# CT_main.net
KiCad netlist of a schematic drawn in EAGLE
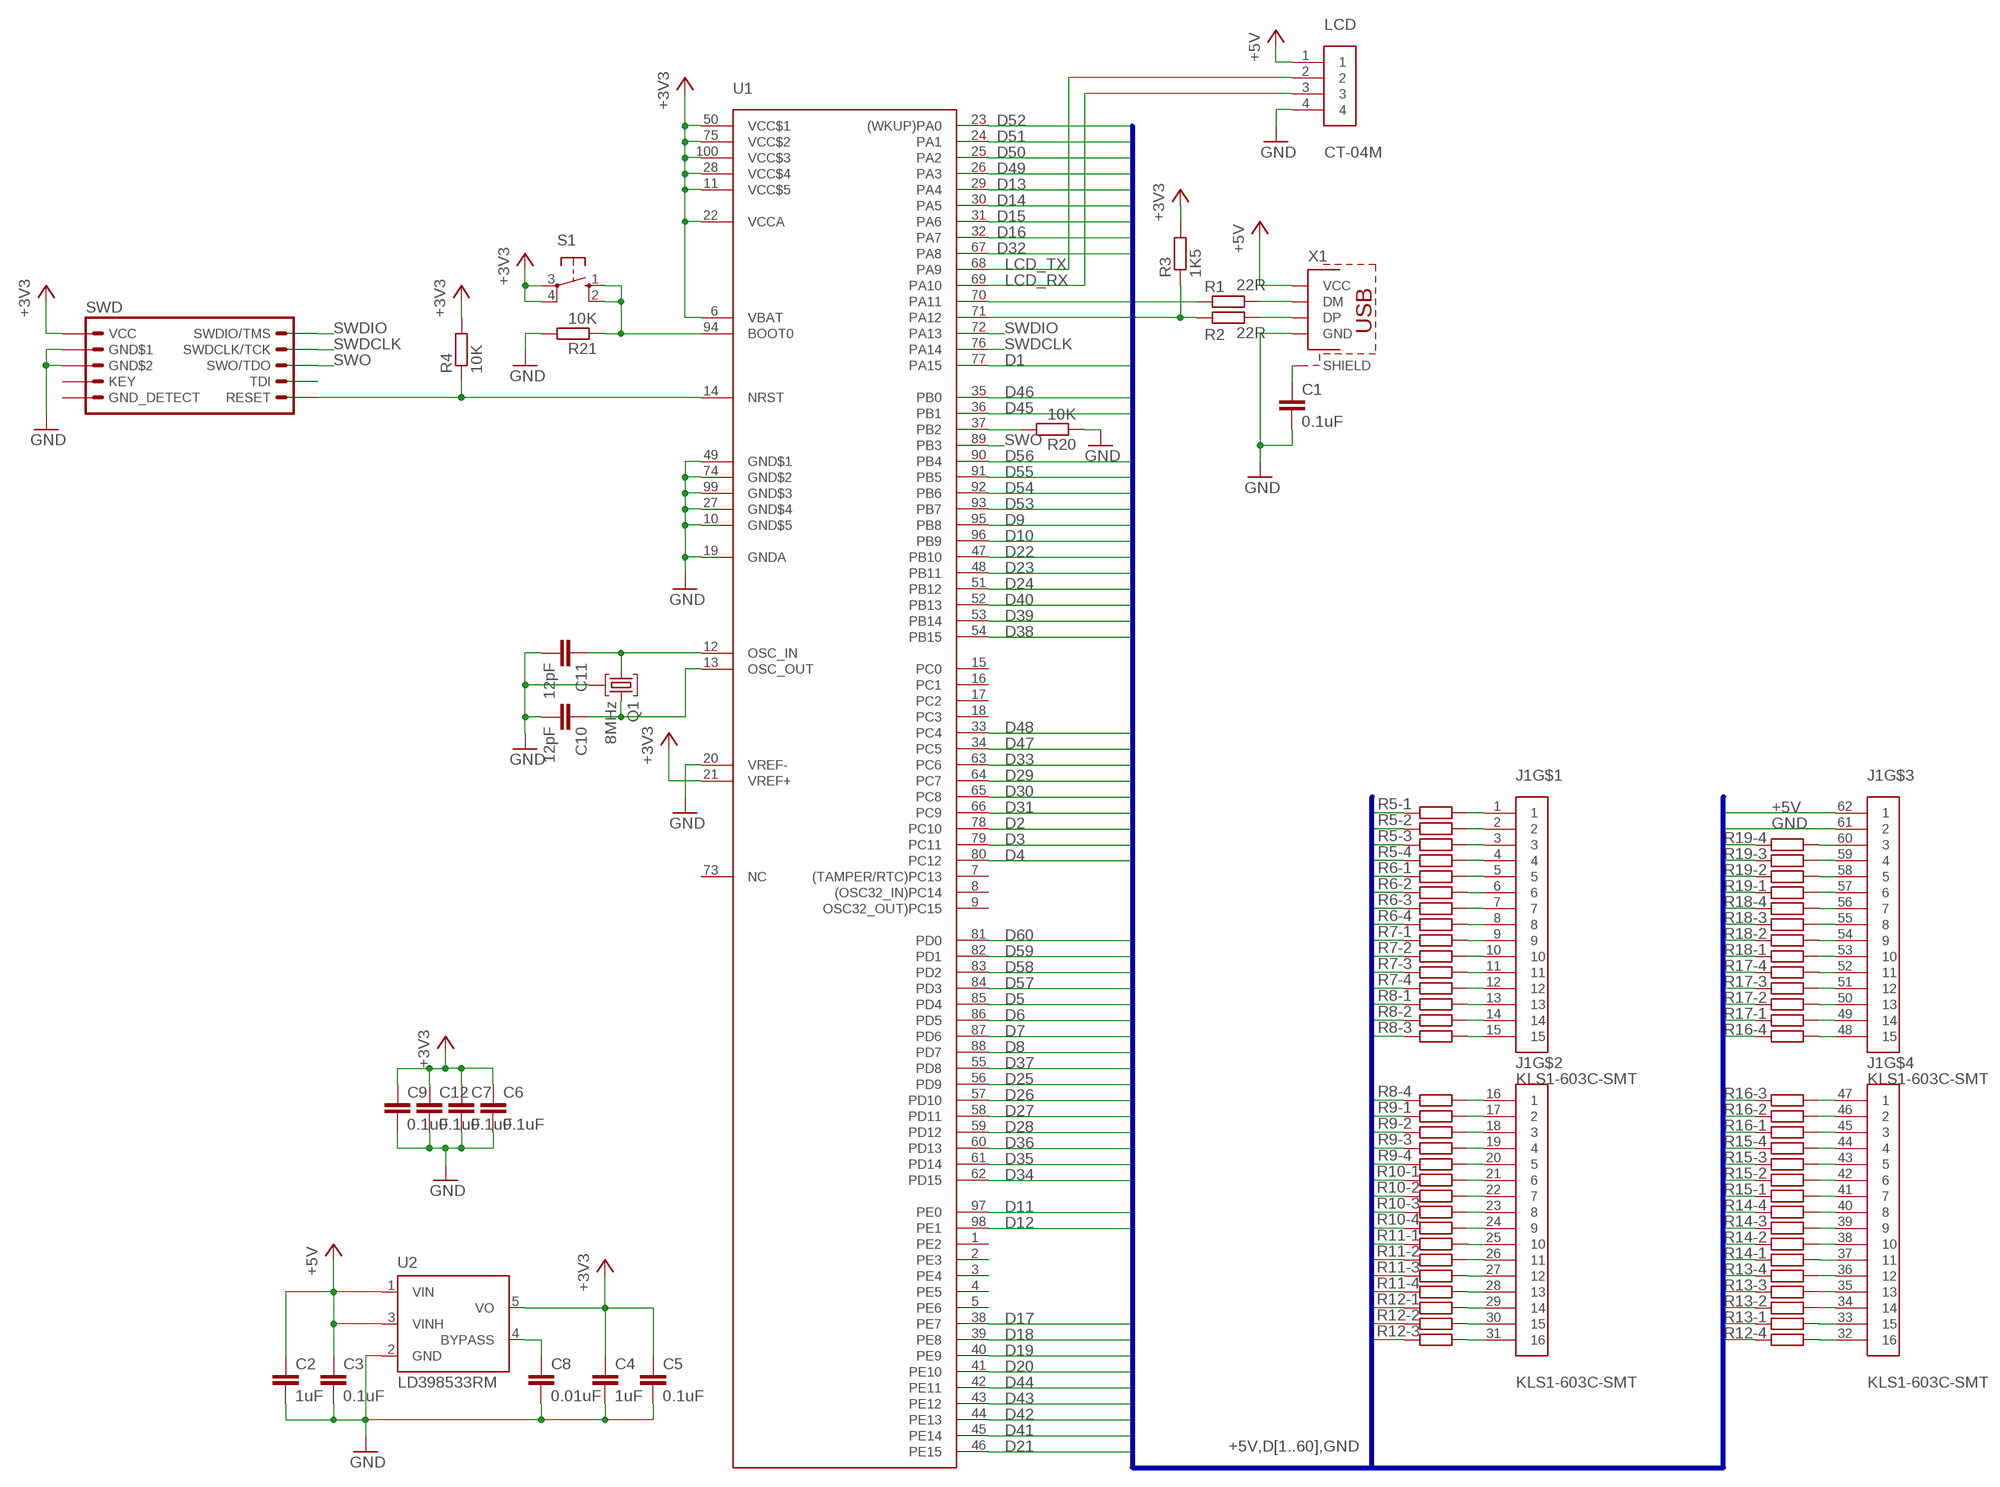
[diagram p0: schematic, sheet 1]

(export (version "E")
  (design (tool "Eeschema 10.0.6"))
  (components
    (comp (ref "C1")
      (value "0.1uF")
      (footprint "eagle-import:C0603")
      (libsource (lib "eagle-import") (part "C-EU_0603"))
    )
    (comp (ref "C2")
      (value "1uF")
      (footprint "eagle-import:C0603")
      (libsource (lib "eagle-import") (part "C-EU_0603"))
    )
    (comp (ref "C3")
      (value "0.1uF")
      (footprint "eagle-import:C0603")
      (libsource (lib "eagle-import") (part "C-EU_0603"))
    )
    (comp (ref "C4")
      (value "1uF")
      (footprint "eagle-import:C0603")
      (libsource (lib "eagle-import") (part "C-EU_0603"))
    )
    (comp (ref "C5")
      (value "0.1uF")
      (footprint "eagle-import:C0603")
      (libsource (lib "eagle-import") (part "C-EU_0603"))
    )
    (comp (ref "C6")
      (value "0.1uF")
      (footprint "eagle-import:C0603")
      (libsource (lib "eagle-import") (part "C-EU_0603"))
    )
    (comp (ref "C7")
      (value "0.1uF")
      (footprint "eagle-import:C0603")
      (libsource (lib "eagle-import") (part "C-EU_0603"))
    )
    (comp (ref "C8")
      (value "0.01uF")
      (footprint "eagle-import:C0603")
      (libsource (lib "eagle-import") (part "C-EU_0603"))
    )
    (comp (ref "C9")
      (value "0.1uF")
      (footprint "eagle-import:C0603")
      (libsource (lib "eagle-import") (part "C-EU_0603"))
    )
    (comp (ref "C10")
      (value "12pF")
      (footprint "eagle-import:C0603")
      (libsource (lib "eagle-import") (part "C-EU_0603"))
    )
    (comp (ref "C11")
      (value "12pF")
      (footprint "eagle-import:C0603")
      (libsource (lib "eagle-import") (part "C-EU_0603"))
    )
    (comp (ref "C12")
      (value "0.1uF")
      (footprint "eagle-import:C0603")
      (libsource (lib "eagle-import") (part "C-EU_0603"))
    )
    (comp (ref "J1")
      (value "KLS1-603C-SMT")
      (footprint "eagle-import:KLS1-603C-SMT")
      (libsource (lib "eagle-import") (part "KLS1-603C-SMT"))
    )
    (comp (ref "LCD")
      (value "CT-04M")
      (footprint "eagle-import:CT-04M")
      (libsource (lib "eagle-import") (part "CT-04M"))
    )
    (comp (ref "Q1")
      (value "8MHz")
      (footprint "eagle-import:KX-7_12.XXXXX")
      (libsource (lib "eagle-import") (part "CRYSTALKX-7_12.XXXXX"))
    )
    (comp (ref "R1")
      (value "22R")
      (footprint "eagle-import:R0603")
      (libsource (lib "eagle-import") (part "R-EU__0603"))
    )
    (comp (ref "R2")
      (value "22R")
      (footprint "eagle-import:R0603")
      (libsource (lib "eagle-import") (part "R-EU__0603"))
    )
    (comp (ref "R3")
      (value "1K5")
      (footprint "eagle-import:R0603")
      (libsource (lib "eagle-import") (part "R-EU__0603"))
    )
    (comp (ref "R4")
      (value "10K")
      (footprint "eagle-import:R0603")
      (libsource (lib "eagle-import") (part "R-EU__0603"))
    )
    (comp (ref "R5")
      (value "R_EU_4_R1206")
      (footprint "eagle-import:R1206_4")
      (libsource (lib "eagle-import") (part "R_EU_4_R1206"))
    )
    (comp (ref "R6")
      (value "R_EU_4_R1206")
      (footprint "eagle-import:R1206_4")
      (libsource (lib "eagle-import") (part "R_EU_4_R1206"))
    )
    (comp (ref "R7")
      (value "R_EU_4_R1206")
      (footprint "eagle-import:R1206_4")
      (libsource (lib "eagle-import") (part "R_EU_4_R1206"))
    )
    (comp (ref "R8")
      (value "R_EU_4_R1206")
      (footprint "eagle-import:R1206_4")
      (libsource (lib "eagle-import") (part "R_EU_4_R1206"))
    )
    (comp (ref "R9")
      (value "R_EU_4_R1206")
      (footprint "eagle-import:R1206_4")
      (libsource (lib "eagle-import") (part "R_EU_4_R1206"))
    )
    (comp (ref "R10")
      (value "R_EU_4_R1206")
      (footprint "eagle-import:R1206_4")
      (libsource (lib "eagle-import") (part "R_EU_4_R1206"))
    )
    (comp (ref "R11")
      (value "R_EU_4_R1206")
      (footprint "eagle-import:R1206_4")
      (libsource (lib "eagle-import") (part "R_EU_4_R1206"))
    )
    (comp (ref "R12")
      (value "R_EU_4_R1206")
      (footprint "eagle-import:R1206_4")
      (libsource (lib "eagle-import") (part "R_EU_4_R1206"))
    )
    (comp (ref "R13")
      (value "R_EU_4_R1206")
      (footprint "eagle-import:R1206_4")
      (libsource (lib "eagle-import") (part "R_EU_4_R1206"))
    )
    (comp (ref "R14")
      (value "R_EU_4_R1206")
      (footprint "eagle-import:R1206_4")
      (libsource (lib "eagle-import") (part "R_EU_4_R1206"))
    )
    (comp (ref "R15")
      (value "R_EU_4_R1206")
      (footprint "eagle-import:R1206_4")
      (libsource (lib "eagle-import") (part "R_EU_4_R1206"))
    )
    (comp (ref "R16")
      (value "R_EU_4_R1206")
      (footprint "eagle-import:R1206_4")
      (libsource (lib "eagle-import") (part "R_EU_4_R1206"))
    )
    (comp (ref "R17")
      (value "R_EU_4_R1206")
      (footprint "eagle-import:R1206_4")
      (libsource (lib "eagle-import") (part "R_EU_4_R1206"))
    )
    (comp (ref "R18")
      (value "R_EU_4_R1206")
      (footprint "eagle-import:R1206_4")
      (libsource (lib "eagle-import") (part "R_EU_4_R1206"))
    )
    (comp (ref "R19")
      (value "R_EU_4_R1206")
      (footprint "eagle-import:R1206_4")
      (libsource (lib "eagle-import") (part "R_EU_4_R1206"))
    )
    (comp (ref "R20")
      (value "10K")
      (footprint "eagle-import:R0603")
      (libsource (lib "eagle-import") (part "R-EU__0603"))
    )
    (comp (ref "R21")
      (value "10K")
      (footprint "eagle-import:R0603")
      (libsource (lib "eagle-import") (part "R-EU__0603"))
    )
    (comp (ref "S1")
      (value "10-XXDTSM-20")
      (footprint "eagle-import:DTSM20")
      (libsource (lib "eagle-import") (part "10-XXDTSM-20"))
    )
    (comp (ref "SWD")
      (value "JTAG/SWD_10PIN")
      (footprint "eagle-import:ML10")
      (libsource (lib "eagle-import") (part "JTAG/SWD_10PIN"))
    )
    (comp (ref "U1")
      (value "STM32F1xx")
      (footprint "eagle-import:LQFP100")
      (libsource (lib "eagle-import") (part "STM32F101XX-LQFP100"))
    )
    (comp (ref "U2")
      (value "LD398533RM")
      (footprint "eagle-import:SOT23-5L")
      (libsource (lib "eagle-import") (part "LD3985M33R"))
    )
    (comp (ref "X1")
      (value "USBMICRO-B")
      (footprint "eagle-import:MOLEX-47364-0001")
      (libsource (lib "eagle-import") (part "USBMICRO-B"))
    )
  )
  (nets
    (net (code "1") (name "+3V3") (class "Default")
      (node (ref "C12") (pin "1") (pinfunction "1_1") (pintype "passive"))
      (node (ref "C4") (pin "1") (pinfunction "1_1") (pintype "passive"))
      (node (ref "C5") (pin "1") (pinfunction "1_1") (pintype "passive"))
      (node (ref "C6") (pin "1") (pinfunction "1_1") (pintype "passive"))
      (node (ref "C7") (pin "1") (pinfunction "1_1") (pintype "passive"))
      (node (ref "C9") (pin "1") (pinfunction "1_1") (pintype "passive"))
      (node (ref "R3") (pin "2") (pinfunction "2_2") (pintype "passive"))
      (node (ref "R4") (pin "2") (pinfunction "2_2") (pintype "passive"))
      (node (ref "S1") (pin "3") (pinfunction "P_3") (pintype "passive"))
      (node (ref "S1") (pin "4") (pinfunction "P1_4") (pintype "passive"))
      (node (ref "SWD") (pin "1") (pinfunction "VCC_1") (pintype "power_in"))
      (node (ref "U1") (pin "100") (pinfunction "VCC$3_100") (pintype "bidirectional"))
      (node (ref "U1") (pin "11") (pinfunction "VCC$5_11") (pintype "bidirectional"))
      (node (ref "U1") (pin "21") (pinfunction "VREF+_21") (pintype "bidirectional"))
      (node (ref "U1") (pin "22") (pinfunction "VCCA_22") (pintype "bidirectional"))
      (node (ref "U1") (pin "28") (pinfunction "VCC$4_28") (pintype "bidirectional"))
      (node (ref "U1") (pin "50") (pinfunction "VCC$1_50") (pintype "bidirectional"))
      (node (ref "U1") (pin "6") (pinfunction "VBAT_6") (pintype "bidirectional"))
      (node (ref "U1") (pin "75") (pinfunction "VCC$2_75") (pintype "bidirectional"))
      (node (ref "U2") (pin "5") (pinfunction "VO_5") (pintype "output"))
    )
    (net (code "2") (name "+5V") (class "Default")
      (node (ref "C2") (pin "1") (pinfunction "1_1") (pintype "passive"))
      (node (ref "C3") (pin "1") (pinfunction "1_1") (pintype "passive"))
      (node (ref "J1") (pin "62") (pinfunction "1_62") (pintype "bidirectional"))
      (node (ref "LCD") (pin "1") (pinfunction "1_1") (pintype "bidirectional"))
      (node (ref "U2") (pin "1") (pinfunction "VIN_1") (pintype "input"))
      (node (ref "U2") (pin "3") (pinfunction "VINH_3") (pintype "input"))
      (node (ref "X1") (pin "1") (pinfunction "VCC_1") (pintype "power_in"))
    )
    (net (code "3") (name "/D1") (class "Default")
      (node (ref "R5") (pin "8") (pinfunction "2_8") (pintype "passive"))
      (node (ref "U1") (pin "77") (pinfunction "PA15_77") (pintype "bidirectional"))
    )
    (net (code "4") (name "/D2") (class "Default")
      (node (ref "R5") (pin "7") (pinfunction "2_7") (pintype "passive"))
      (node (ref "U1") (pin "78") (pinfunction "PC10_78") (pintype "bidirectional"))
    )
    (net (code "5") (name "/D3") (class "Default")
      (node (ref "R5") (pin "6") (pinfunction "2_6") (pintype "passive"))
      (node (ref "U1") (pin "79") (pinfunction "PC11_79") (pintype "bidirectional"))
    )
    (net (code "6") (name "/D4") (class "Default")
      (node (ref "R5") (pin "5") (pinfunction "2_5") (pintype "passive"))
      (node (ref "U1") (pin "80") (pinfunction "PC12_80") (pintype "bidirectional"))
    )
    (net (code "7") (name "/D5") (class "Default")
      (node (ref "R6") (pin "8") (pinfunction "2_8") (pintype "passive"))
      (node (ref "U1") (pin "85") (pinfunction "PD4_85") (pintype "bidirectional"))
    )
    (net (code "8") (name "/D6") (class "Default")
      (node (ref "R6") (pin "7") (pinfunction "2_7") (pintype "passive"))
      (node (ref "U1") (pin "86") (pinfunction "PD5_86") (pintype "bidirectional"))
    )
    (net (code "9") (name "/D7") (class "Default")
      (node (ref "R6") (pin "6") (pinfunction "2_6") (pintype "passive"))
      (node (ref "U1") (pin "87") (pinfunction "PD6_87") (pintype "bidirectional"))
    )
    (net (code "10") (name "/D8") (class "Default")
      (node (ref "R6") (pin "5") (pinfunction "2_5") (pintype "passive"))
      (node (ref "U1") (pin "88") (pinfunction "PD7_88") (pintype "bidirectional"))
    )
    (net (code "11") (name "/D9") (class "Default")
      (node (ref "R7") (pin "8") (pinfunction "2_8") (pintype "passive"))
      (node (ref "U1") (pin "95") (pinfunction "PB8_95") (pintype "bidirectional"))
    )
    (net (code "12") (name "/D10") (class "Default")
      (node (ref "R7") (pin "7") (pinfunction "2_7") (pintype "passive"))
      (node (ref "U1") (pin "96") (pinfunction "PB9_96") (pintype "bidirectional"))
    )
    (net (code "13") (name "/D11") (class "Default")
      (node (ref "R7") (pin "6") (pinfunction "2_6") (pintype "passive"))
      (node (ref "U1") (pin "97") (pinfunction "PE0_97") (pintype "bidirectional"))
    )
    (net (code "14") (name "/D12") (class "Default")
      (node (ref "R7") (pin "5") (pinfunction "2_5") (pintype "passive"))
      (node (ref "U1") (pin "98") (pinfunction "PE1_98") (pintype "bidirectional"))
    )
    (net (code "15") (name "/D13") (class "Default")
      (node (ref "R8") (pin "8") (pinfunction "2_8") (pintype "passive"))
      (node (ref "U1") (pin "29") (pinfunction "PA4_29") (pintype "bidirectional"))
    )
    (net (code "16") (name "/D14") (class "Default")
      (node (ref "R8") (pin "7") (pinfunction "2_7") (pintype "passive"))
      (node (ref "U1") (pin "30") (pinfunction "PA5_30") (pintype "bidirectional"))
    )
    (net (code "17") (name "/D15") (class "Default")
      (node (ref "R8") (pin "6") (pinfunction "2_6") (pintype "passive"))
      (node (ref "U1") (pin "31") (pinfunction "PA6_31") (pintype "bidirectional"))
    )
    (net (code "18") (name "/D16") (class "Default")
      (node (ref "R8") (pin "5") (pinfunction "2_5") (pintype "passive"))
      (node (ref "U1") (pin "32") (pinfunction "PA7_32") (pintype "bidirectional"))
    )
    (net (code "19") (name "/D17") (class "Default")
      (node (ref "R9") (pin "8") (pinfunction "2_8") (pintype "passive"))
      (node (ref "U1") (pin "38") (pinfunction "PE7_38") (pintype "bidirectional"))
    )
    (net (code "20") (name "/D18") (class "Default")
      (node (ref "R9") (pin "7") (pinfunction "2_7") (pintype "passive"))
      (node (ref "U1") (pin "39") (pinfunction "PE8_39") (pintype "bidirectional"))
    )
    (net (code "21") (name "/D19") (class "Default")
      (node (ref "R9") (pin "6") (pinfunction "2_6") (pintype "passive"))
      (node (ref "U1") (pin "40") (pinfunction "PE9_40") (pintype "bidirectional"))
    )
    (net (code "22") (name "/D20") (class "Default")
      (node (ref "R9") (pin "5") (pinfunction "2_5") (pintype "passive"))
      (node (ref "U1") (pin "41") (pinfunction "PE10_41") (pintype "bidirectional"))
    )
    (net (code "23") (name "/D21") (class "Default")
      (node (ref "R10") (pin "8") (pinfunction "2_8") (pintype "passive"))
      (node (ref "U1") (pin "46") (pinfunction "PE15_46") (pintype "bidirectional"))
    )
    (net (code "24") (name "/D22") (class "Default")
      (node (ref "R10") (pin "7") (pinfunction "2_7") (pintype "passive"))
      (node (ref "U1") (pin "47") (pinfunction "PB10_47") (pintype "bidirectional"))
    )
    (net (code "25") (name "/D23") (class "Default")
      (node (ref "R10") (pin "6") (pinfunction "2_6") (pintype "passive"))
      (node (ref "U1") (pin "48") (pinfunction "PB11_48") (pintype "bidirectional"))
    )
    (net (code "26") (name "/D24") (class "Default")
      (node (ref "R10") (pin "5") (pinfunction "2_5") (pintype "passive"))
      (node (ref "U1") (pin "51") (pinfunction "PB12_51") (pintype "bidirectional"))
    )
    (net (code "27") (name "/D25") (class "Default")
      (node (ref "R11") (pin "8") (pinfunction "2_8") (pintype "passive"))
      (node (ref "U1") (pin "56") (pinfunction "PD9_56") (pintype "bidirectional"))
    )
    (net (code "28") (name "/D26") (class "Default")
      (node (ref "R11") (pin "7") (pinfunction "2_7") (pintype "passive"))
      (node (ref "U1") (pin "57") (pinfunction "PD10_57") (pintype "bidirectional"))
    )
    (net (code "29") (name "/D27") (class "Default")
      (node (ref "R11") (pin "6") (pinfunction "2_6") (pintype "passive"))
      (node (ref "U1") (pin "58") (pinfunction "PD11_58") (pintype "bidirectional"))
    )
    (net (code "30") (name "/D28") (class "Default")
      (node (ref "R11") (pin "5") (pinfunction "2_5") (pintype "passive"))
      (node (ref "U1") (pin "59") (pinfunction "PD12_59") (pintype "bidirectional"))
    )
    (net (code "31") (name "/D29") (class "Default")
      (node (ref "R12") (pin "8") (pinfunction "2_8") (pintype "passive"))
      (node (ref "U1") (pin "64") (pinfunction "PC7_64") (pintype "bidirectional"))
    )
    (net (code "32") (name "/D30") (class "Default")
      (node (ref "R12") (pin "7") (pinfunction "2_7") (pintype "passive"))
      (node (ref "U1") (pin "65") (pinfunction "PC8_65") (pintype "bidirectional"))
    )
    (net (code "33") (name "/D31") (class "Default")
      (node (ref "R12") (pin "6") (pinfunction "2_6") (pintype "passive"))
      (node (ref "U1") (pin "66") (pinfunction "PC9_66") (pintype "bidirectional"))
    )
    (net (code "34") (name "/D32") (class "Default")
      (node (ref "R12") (pin "5") (pinfunction "2_5") (pintype "passive"))
      (node (ref "U1") (pin "67") (pinfunction "PA8_67") (pintype "bidirectional"))
    )
    (net (code "35") (name "/D33") (class "Default")
      (node (ref "R13") (pin "1") (pinfunction "1_1") (pintype "passive"))
      (node (ref "U1") (pin "63") (pinfunction "PC6_63") (pintype "bidirectional"))
    )
    (net (code "36") (name "/D34") (class "Default")
      (node (ref "R13") (pin "2") (pinfunction "1_2") (pintype "passive"))
      (node (ref "U1") (pin "62") (pinfunction "PD15_62") (pintype "bidirectional"))
    )
    (net (code "37") (name "/D35") (class "Default")
      (node (ref "R13") (pin "3") (pinfunction "1_3") (pintype "passive"))
      (node (ref "U1") (pin "61") (pinfunction "PD14_61") (pintype "bidirectional"))
    )
    (net (code "38") (name "/D36") (class "Default")
      (node (ref "R13") (pin "4") (pinfunction "1_4") (pintype "passive"))
      (node (ref "U1") (pin "60") (pinfunction "PD13_60") (pintype "bidirectional"))
    )
    (net (code "39") (name "/D37") (class "Default")
      (node (ref "R14") (pin "1") (pinfunction "1_1") (pintype "passive"))
      (node (ref "U1") (pin "55") (pinfunction "PD8_55") (pintype "bidirectional"))
    )
    (net (code "40") (name "/D38") (class "Default")
      (node (ref "R14") (pin "2") (pinfunction "1_2") (pintype "passive"))
      (node (ref "U1") (pin "54") (pinfunction "PB15_54") (pintype "bidirectional"))
    )
    (net (code "41") (name "/D39") (class "Default")
      (node (ref "R14") (pin "3") (pinfunction "1_3") (pintype "passive"))
      (node (ref "U1") (pin "53") (pinfunction "PB14_53") (pintype "bidirectional"))
    )
    (net (code "42") (name "/D40") (class "Default")
      (node (ref "R14") (pin "4") (pinfunction "1_4") (pintype "passive"))
      (node (ref "U1") (pin "52") (pinfunction "PB13_52") (pintype "bidirectional"))
    )
    (net (code "43") (name "/D41") (class "Default")
      (node (ref "R15") (pin "1") (pinfunction "1_1") (pintype "passive"))
      (node (ref "U1") (pin "45") (pinfunction "PE14_45") (pintype "bidirectional"))
    )
    (net (code "44") (name "/D42") (class "Default")
      (node (ref "R15") (pin "2") (pinfunction "1_2") (pintype "passive"))
      (node (ref "U1") (pin "44") (pinfunction "PE13_44") (pintype "bidirectional"))
    )
    (net (code "45") (name "/D43") (class "Default")
      (node (ref "R15") (pin "3") (pinfunction "1_3") (pintype "passive"))
      (node (ref "U1") (pin "43") (pinfunction "PE12_43") (pintype "bidirectional"))
    )
    (net (code "46") (name "/D44") (class "Default")
      (node (ref "R15") (pin "4") (pinfunction "1_4") (pintype "passive"))
      (node (ref "U1") (pin "42") (pinfunction "PE11_42") (pintype "bidirectional"))
    )
    (net (code "47") (name "/D45") (class "Default")
      (node (ref "R16") (pin "1") (pinfunction "1_1") (pintype "passive"))
      (node (ref "U1") (pin "36") (pinfunction "PB1_36") (pintype "bidirectional"))
    )
    (net (code "48") (name "/D46") (class "Default")
      (node (ref "R16") (pin "2") (pinfunction "1_2") (pintype "passive"))
      (node (ref "U1") (pin "35") (pinfunction "PB0_35") (pintype "bidirectional"))
    )
    (net (code "49") (name "/D47") (class "Default")
      (node (ref "R16") (pin "3") (pinfunction "1_3") (pintype "passive"))
      (node (ref "U1") (pin "34") (pinfunction "PC5_34") (pintype "bidirectional"))
    )
    (net (code "50") (name "/D48") (class "Default")
      (node (ref "R16") (pin "4") (pinfunction "1_4") (pintype "passive"))
      (node (ref "U1") (pin "33") (pinfunction "PC4_33") (pintype "bidirectional"))
    )
    (net (code "51") (name "/D49") (class "Default")
      (node (ref "R17") (pin "1") (pinfunction "1_1") (pintype "passive"))
      (node (ref "U1") (pin "26") (pinfunction "PA3_26") (pintype "bidirectional"))
    )
    (net (code "52") (name "/D50") (class "Default")
      (node (ref "R17") (pin "2") (pinfunction "1_2") (pintype "passive"))
      (node (ref "U1") (pin "25") (pinfunction "PA2_25") (pintype "bidirectional"))
    )
    (net (code "53") (name "/D51") (class "Default")
      (node (ref "R17") (pin "3") (pinfunction "1_3") (pintype "passive"))
      (node (ref "U1") (pin "24") (pinfunction "PA1_24") (pintype "bidirectional"))
    )
    (net (code "54") (name "/D52") (class "Default")
      (node (ref "R17") (pin "4") (pinfunction "1_4") (pintype "passive"))
      (node (ref "U1") (pin "23") (pinfunction "(WKUP)PA0_23") (pintype "bidirectional"))
    )
    (net (code "55") (name "/D53") (class "Default")
      (node (ref "R18") (pin "1") (pinfunction "1_1") (pintype "passive"))
      (node (ref "U1") (pin "93") (pinfunction "PB7_93") (pintype "bidirectional"))
    )
    (net (code "56") (name "/D54") (class "Default")
      (node (ref "R18") (pin "2") (pinfunction "1_2") (pintype "passive"))
      (node (ref "U1") (pin "92") (pinfunction "PB6_92") (pintype "bidirectional"))
    )
    (net (code "57") (name "/D55") (class "Default")
      (node (ref "R18") (pin "3") (pinfunction "1_3") (pintype "passive"))
      (node (ref "U1") (pin "91") (pinfunction "PB5_91") (pintype "bidirectional"))
    )
    (net (code "58") (name "/D56") (class "Default")
      (node (ref "R18") (pin "4") (pinfunction "1_4") (pintype "passive"))
      (node (ref "U1") (pin "90") (pinfunction "PB4_90") (pintype "bidirectional"))
    )
    (net (code "59") (name "/D57") (class "Default")
      (node (ref "R19") (pin "1") (pinfunction "1_1") (pintype "passive"))
      (node (ref "U1") (pin "84") (pinfunction "PD3_84") (pintype "bidirectional"))
    )
    (net (code "60") (name "/D58") (class "Default")
      (node (ref "R19") (pin "2") (pinfunction "1_2") (pintype "passive"))
      (node (ref "U1") (pin "83") (pinfunction "PD2_83") (pintype "bidirectional"))
    )
    (net (code "61") (name "/D59") (class "Default")
      (node (ref "R19") (pin "3") (pinfunction "1_3") (pintype "passive"))
      (node (ref "U1") (pin "82") (pinfunction "PD1_82") (pintype "bidirectional"))
    )
    (net (code "62") (name "/D60") (class "Default")
      (node (ref "R19") (pin "4") (pinfunction "1_4") (pintype "passive"))
      (node (ref "U1") (pin "81") (pinfunction "PD0_81") (pintype "bidirectional"))
    )
    (net (code "63") (name "/GND_DETECT") (class "Default")
      (node (ref "SWD") (pin "9") (pinfunction "GND_DETECT_9") (pintype "power_in"))
    )
    (net (code "64") (name "/LCD_RX") (class "Default")
      (node (ref "LCD") (pin "3") (pinfunction "3_3") (pintype "bidirectional"))
      (node (ref "U1") (pin "69") (pinfunction "PA10_69") (pintype "bidirectional"))
    )
    (net (code "65") (name "/LCD_TX") (class "Default")
      (node (ref "LCD") (pin "2") (pinfunction "2_2") (pintype "bidirectional"))
      (node (ref "U1") (pin "68") (pinfunction "PA9_68") (pintype "bidirectional"))
    )
    (net (code "66") (name "/SWDCLK") (class "Default")
      (node (ref "SWD") (pin "4") (pinfunction "SWDCLK/TCK_4") (pintype "bidirectional"))
      (node (ref "U1") (pin "76") (pinfunction "PA14_76") (pintype "bidirectional"))
    )
    (net (code "67") (name "/SWDIO") (class "Default")
      (node (ref "SWD") (pin "2") (pinfunction "SWDIO/TMS_2") (pintype "bidirectional"))
      (node (ref "U1") (pin "72") (pinfunction "PA13_72") (pintype "bidirectional"))
    )
    (net (code "68") (name "/SWO") (class "Default")
      (node (ref "SWD") (pin "6") (pinfunction "SWO/TDO_6") (pintype "bidirectional"))
      (node (ref "U1") (pin "89") (pinfunction "PB3_89") (pintype "bidirectional"))
    )
    (net (code "70") (name "GND") (class "Default")
      (node (ref "C1") (pin "2") (pinfunction "2_2") (pintype "passive"))
      (node (ref "C10") (pin "2") (pinfunction "2_2") (pintype "passive"))
      (node (ref "C11") (pin "2") (pinfunction "2_2") (pintype "passive"))
      (node (ref "C12") (pin "2") (pinfunction "2_2") (pintype "passive"))
      (node (ref "C2") (pin "2") (pinfunction "2_2") (pintype "passive"))
      (node (ref "C3") (pin "2") (pinfunction "2_2") (pintype "passive"))
      (node (ref "C4") (pin "2") (pinfunction "2_2") (pintype "passive"))
      (node (ref "C5") (pin "2") (pinfunction "2_2") (pintype "passive"))
      (node (ref "C6") (pin "2") (pinfunction "2_2") (pintype "passive"))
      (node (ref "C7") (pin "2") (pinfunction "2_2") (pintype "passive"))
      (node (ref "C8") (pin "2") (pinfunction "2_2") (pintype "passive"))
      (node (ref "C9") (pin "2") (pinfunction "2_2") (pintype "passive"))
      (node (ref "J1") (pin "61") (pinfunction "2_61") (pintype "bidirectional"))
      (node (ref "LCD") (pin "4") (pinfunction "4_4") (pintype "bidirectional"))
      (node (ref "Q1") (pin "2") (pinfunction "2_2") (pintype "passive"))
      (node (ref "Q1") (pin "4") (pinfunction "2_4") (pintype "passive"))
      (node (ref "R20") (pin "1") (pinfunction "1_1") (pintype "passive"))
      (node (ref "R21") (pin "2") (pinfunction "2_2") (pintype "passive"))
      (node (ref "SWD") (pin "3") (pinfunction "GND$1_3") (pintype "power_in"))
      (node (ref "SWD") (pin "5") (pinfunction "GND$2_5") (pintype "power_in"))
      (node (ref "U1") (pin "10") (pinfunction "GND$5_10") (pintype "bidirectional"))
      (node (ref "U1") (pin "19") (pinfunction "GNDA_19") (pintype "bidirectional"))
      (node (ref "U1") (pin "20") (pinfunction "VREF-_20") (pintype "bidirectional"))
      (node (ref "U1") (pin "27") (pinfunction "GND$4_27") (pintype "bidirectional"))
      (node (ref "U1") (pin "49") (pinfunction "GND$1_49") (pintype "bidirectional"))
      (node (ref "U1") (pin "74") (pinfunction "GND$2_74") (pintype "bidirectional"))
      (node (ref "U1") (pin "99") (pinfunction "GND$3_99") (pintype "bidirectional"))
      (node (ref "U2") (pin "2") (pinfunction "GND_2") (pintype "power_in"))
      (node (ref "X1") (pin "5") (pinfunction "GND_5") (pintype "power_in"))
    )
    (net (code "71") (name "Net-(C1-Pad1)") (class "Default")
      (node (ref "C1") (pin "1") (pinfunction "1_1") (pintype "passive"))
      (node (ref "X1") (pin "GND1") (pinfunction "SHIELD_GND1") (pintype "power_in"))
      (node (ref "X1") (pin "GND2") (pinfunction "SHIELD_GND2") (pintype "power_in"))
      (node (ref "X1") (pin "GND3") (pinfunction "SHIELD_GND3") (pintype "power_in"))
      (node (ref "X1") (pin "GND4") (pinfunction "SHIELD_GND4") (pintype "power_in"))
    )
    (net (code "72") (name "Net-(J1-Pad1)") (class "Default")
      (node (ref "J1") (pin "1") (pinfunction "1_1") (pintype "bidirectional"))
      (node (ref "R5") (pin "1") (pinfunction "1_1") (pintype "passive"))
    )
    (net (code "73") (name "Net-(J1-Pad5)") (class "Default")
      (node (ref "J1") (pin "5") (pinfunction "5_5") (pintype "bidirectional"))
      (node (ref "R6") (pin "1") (pinfunction "1_1") (pintype "passive"))
    )
    (net (code "74") (name "Net-(J1-Pad9)") (class "Default")
      (node (ref "J1") (pin "9") (pinfunction "9_9") (pintype "bidirectional"))
      (node (ref "R7") (pin "1") (pinfunction "1_1") (pintype "passive"))
    )
    (net (code "75") (name "Net-(J1-Pad13)") (class "Default")
      (node (ref "J1") (pin "13") (pinfunction "13_13") (pintype "bidirectional"))
      (node (ref "R8") (pin "1") (pinfunction "1_1") (pintype "passive"))
    )
    (net (code "76") (name "Net-(J1B-1)") (class "Default")
      (node (ref "J1") (pin "16") (pinfunction "1_16") (pintype "bidirectional"))
      (node (ref "R8") (pin "4") (pinfunction "1_4") (pintype "passive"))
    )
    (net (code "77") (name "Net-(J1B-2)") (class "Default")
      (node (ref "J1") (pin "17") (pinfunction "2_17") (pintype "bidirectional"))
      (node (ref "R9") (pin "1") (pinfunction "1_1") (pintype "passive"))
    )
    (net (code "78") (name "Net-(J1B-3)") (class "Default")
      (node (ref "J1") (pin "18") (pinfunction "3_18") (pintype "bidirectional"))
      (node (ref "R9") (pin "2") (pinfunction "1_2") (pintype "passive"))
    )
    (net (code "79") (name "Net-(J1B-4)") (class "Default")
      (node (ref "J1") (pin "19") (pinfunction "4_19") (pintype "bidirectional"))
      (node (ref "R9") (pin "3") (pinfunction "1_3") (pintype "passive"))
    )
    (net (code "80") (name "Net-(J1B-5)") (class "Default")
      (node (ref "J1") (pin "20") (pinfunction "5_20") (pintype "bidirectional"))
      (node (ref "R9") (pin "4") (pinfunction "1_4") (pintype "passive"))
    )
    (net (code "81") (name "Net-(J1B-6)") (class "Default")
      (node (ref "J1") (pin "21") (pinfunction "6_21") (pintype "bidirectional"))
      (node (ref "R10") (pin "1") (pinfunction "1_1") (pintype "passive"))
    )
    (net (code "82") (name "Net-(J1B-7)") (class "Default")
      (node (ref "J1") (pin "22") (pinfunction "7_22") (pintype "bidirectional"))
      (node (ref "R10") (pin "2") (pinfunction "1_2") (pintype "passive"))
    )
    (net (code "83") (name "Net-(J1B-8)") (class "Default")
      (node (ref "J1") (pin "23") (pinfunction "8_23") (pintype "bidirectional"))
      (node (ref "R10") (pin "3") (pinfunction "1_3") (pintype "passive"))
    )
    (net (code "84") (name "Net-(J1B-9)") (class "Default")
      (node (ref "J1") (pin "24") (pinfunction "9_24") (pintype "bidirectional"))
      (node (ref "R10") (pin "4") (pinfunction "1_4") (pintype "passive"))
    )
    (net (code "85") (name "Net-(J1B-10)") (class "Default")
      (node (ref "J1") (pin "25") (pinfunction "10_25") (pintype "bidirectional"))
      (node (ref "R11") (pin "1") (pinfunction "1_1") (pintype "passive"))
    )
    (net (code "86") (name "Net-(J1B-11)") (class "Default")
      (node (ref "J1") (pin "26") (pinfunction "11_26") (pintype "bidirectional"))
      (node (ref "R11") (pin "2") (pinfunction "1_2") (pintype "passive"))
    )
    (net (code "87") (name "Net-(J1B-12)") (class "Default")
      (node (ref "J1") (pin "27") (pinfunction "12_27") (pintype "bidirectional"))
      (node (ref "R11") (pin "3") (pinfunction "1_3") (pintype "passive"))
    )
    (net (code "88") (name "Net-(J1B-13)") (class "Default")
      (node (ref "J1") (pin "28") (pinfunction "13_28") (pintype "bidirectional"))
      (node (ref "R11") (pin "4") (pinfunction "1_4") (pintype "passive"))
    )
    (net (code "89") (name "Net-(J1B-14)") (class "Default")
      (node (ref "J1") (pin "29") (pinfunction "14_29") (pintype "bidirectional"))
      (node (ref "R12") (pin "1") (pinfunction "1_1") (pintype "passive"))
    )
    (net (code "90") (name "Net-(J1B-15)") (class "Default")
      (node (ref "J1") (pin "30") (pinfunction "15_30") (pintype "bidirectional"))
      (node (ref "R12") (pin "2") (pinfunction "1_2") (pintype "passive"))
    )
    (net (code "91") (name "Net-(J1B-16)") (class "Default")
      (node (ref "J1") (pin "31") (pinfunction "16_31") (pintype "bidirectional"))
      (node (ref "R12") (pin "3") (pinfunction "1_3") (pintype "passive"))
    )
    (net (code "92") (name "Net-(J1C-3)") (class "Default")
      (node (ref "J1") (pin "60") (pinfunction "3_60") (pintype "bidirectional"))
      (node (ref "R19") (pin "5") (pinfunction "2_5") (pintype "passive"))
    )
    (net (code "93") (name "Net-(J1C-4)") (class "Default")
      (node (ref "J1") (pin "59") (pinfunction "4_59") (pintype "bidirectional"))
      (node (ref "R19") (pin "6") (pinfunction "2_6") (pintype "passive"))
    )
    (net (code "94") (name "Net-(J1C-5)") (class "Default")
      (node (ref "J1") (pin "58") (pinfunction "5_58") (pintype "bidirectional"))
      (node (ref "R19") (pin "7") (pinfunction "2_7") (pintype "passive"))
    )
    (net (code "95") (name "Net-(J1C-6)") (class "Default")
      (node (ref "J1") (pin "57") (pinfunction "6_57") (pintype "bidirectional"))
      (node (ref "R19") (pin "8") (pinfunction "2_8") (pintype "passive"))
    )
    (net (code "96") (name "Net-(J1C-7)") (class "Default")
      (node (ref "J1") (pin "56") (pinfunction "7_56") (pintype "bidirectional"))
      (node (ref "R18") (pin "5") (pinfunction "2_5") (pintype "passive"))
    )
    (net (code "97") (name "Net-(J1C-8)") (class "Default")
      (node (ref "J1") (pin "55") (pinfunction "8_55") (pintype "bidirectional"))
      (node (ref "R18") (pin "6") (pinfunction "2_6") (pintype "passive"))
    )
    (net (code "98") (name "Net-(J1C-9)") (class "Default")
      (node (ref "J1") (pin "54") (pinfunction "9_54") (pintype "bidirectional"))
      (node (ref "R18") (pin "7") (pinfunction "2_7") (pintype "passive"))
    )
    (net (code "99") (name "Net-(J1C-10)") (class "Default")
      (node (ref "J1") (pin "53") (pinfunction "10_53") (pintype "bidirectional"))
      (node (ref "R18") (pin "8") (pinfunction "2_8") (pintype "passive"))
    )
    (net (code "100") (name "Net-(J1C-11)") (class "Default")
      (node (ref "J1") (pin "52") (pinfunction "11_52") (pintype "bidirectional"))
      (node (ref "R17") (pin "5") (pinfunction "2_5") (pintype "passive"))
    )
    (net (code "101") (name "Net-(J1C-12)") (class "Default")
      (node (ref "J1") (pin "51") (pinfunction "12_51") (pintype "bidirectional"))
      (node (ref "R17") (pin "6") (pinfunction "2_6") (pintype "passive"))
    )
    (net (code "102") (name "Net-(J1C-13)") (class "Default")
      (node (ref "J1") (pin "50") (pinfunction "13_50") (pintype "bidirectional"))
      (node (ref "R17") (pin "7") (pinfunction "2_7") (pintype "passive"))
    )
    (net (code "103") (name "Net-(J1C-14)") (class "Default")
      (node (ref "J1") (pin "49") (pinfunction "14_49") (pintype "bidirectional"))
      (node (ref "R17") (pin "8") (pinfunction "2_8") (pintype "passive"))
    )
    (net (code "104") (name "Net-(J1C-15)") (class "Default")
      (node (ref "J1") (pin "48") (pinfunction "15_48") (pintype "bidirectional"))
      (node (ref "R16") (pin "5") (pinfunction "2_5") (pintype "passive"))
    )
    (net (code "105") (name "Net-(J1D-1)") (class "Default")
      (node (ref "J1") (pin "47") (pinfunction "1_47") (pintype "bidirectional"))
      (node (ref "R16") (pin "6") (pinfunction "2_6") (pintype "passive"))
    )
    (net (code "106") (name "Net-(J1D-2)") (class "Default")
      (node (ref "J1") (pin "46") (pinfunction "2_46") (pintype "bidirectional"))
      (node (ref "R16") (pin "7") (pinfunction "2_7") (pintype "passive"))
    )
    (net (code "107") (name "Net-(J1D-3)") (class "Default")
      (node (ref "J1") (pin "45") (pinfunction "3_45") (pintype "bidirectional"))
      (node (ref "R16") (pin "8") (pinfunction "2_8") (pintype "passive"))
    )
    (net (code "108") (name "Net-(J1D-4)") (class "Default")
      (node (ref "J1") (pin "44") (pinfunction "4_44") (pintype "bidirectional"))
      (node (ref "R15") (pin "5") (pinfunction "2_5") (pintype "passive"))
    )
    (net (code "109") (name "Net-(J1D-5)") (class "Default")
      (node (ref "J1") (pin "43") (pinfunction "5_43") (pintype "bidirectional"))
      (node (ref "R15") (pin "6") (pinfunction "2_6") (pintype "passive"))
    )
    (net (code "110") (name "Net-(J1D-6)") (class "Default")
      (node (ref "J1") (pin "42") (pinfunction "6_42") (pintype "bidirectional"))
      (node (ref "R15") (pin "7") (pinfunction "2_7") (pintype "passive"))
    )
    (net (code "111") (name "Net-(J1D-7)") (class "Default")
      (node (ref "J1") (pin "41") (pinfunction "7_41") (pintype "bidirectional"))
      (node (ref "R15") (pin "8") (pinfunction "2_8") (pintype "passive"))
    )
    (net (code "112") (name "Net-(J1D-8)") (class "Default")
      (node (ref "J1") (pin "40") (pinfunction "8_40") (pintype "bidirectional"))
      (node (ref "R14") (pin "5") (pinfunction "2_5") (pintype "passive"))
    )
    (net (code "113") (name "Net-(J1D-9)") (class "Default")
      (node (ref "J1") (pin "39") (pinfunction "9_39") (pintype "bidirectional"))
      (node (ref "R14") (pin "6") (pinfunction "2_6") (pintype "passive"))
    )
    (net (code "114") (name "Net-(J1D-10)") (class "Default")
      (node (ref "J1") (pin "38") (pinfunction "10_38") (pintype "bidirectional"))
      (node (ref "R14") (pin "7") (pinfunction "2_7") (pintype "passive"))
    )
    (net (code "115") (name "Net-(J1D-11)") (class "Default")
      (node (ref "J1") (pin "37") (pinfunction "11_37") (pintype "bidirectional"))
      (node (ref "R14") (pin "8") (pinfunction "2_8") (pintype "passive"))
    )
    (net (code "116") (name "Net-(J1D-12)") (class "Default")
      (node (ref "J1") (pin "36") (pinfunction "12_36") (pintype "bidirectional"))
      (node (ref "R13") (pin "5") (pinfunction "2_5") (pintype "passive"))
    )
    (net (code "117") (name "Net-(J1D-13)") (class "Default")
      (node (ref "J1") (pin "35") (pinfunction "13_35") (pintype "bidirectional"))
      (node (ref "R13") (pin "6") (pinfunction "2_6") (pintype "passive"))
    )
    (net (code "118") (name "Net-(J1D-14)") (class "Default")
      (node (ref "J1") (pin "34") (pinfunction "14_34") (pintype "bidirectional"))
      (node (ref "R13") (pin "7") (pinfunction "2_7") (pintype "passive"))
    )
    (net (code "119") (name "Net-(J1D-15)") (class "Default")
      (node (ref "J1") (pin "33") (pinfunction "15_33") (pintype "bidirectional"))
      (node (ref "R13") (pin "8") (pinfunction "2_8") (pintype "passive"))
    )
    (net (code "120") (name "Net-(J1D-16)") (class "Default")
      (node (ref "J1") (pin "32") (pinfunction "16_32") (pintype "bidirectional"))
      (node (ref "R12") (pin "4") (pinfunction "1_4") (pintype "passive"))
    )
    (net (code "121") (name "Net-(R5B-1)") (class "Default")
      (node (ref "J1") (pin "2") (pinfunction "2_2") (pintype "bidirectional"))
      (node (ref "R5") (pin "2") (pinfunction "1_2") (pintype "passive"))
    )
    (net (code "122") (name "Net-(R5C-1)") (class "Default")
      (node (ref "J1") (pin "3") (pinfunction "3_3") (pintype "bidirectional"))
      (node (ref "R5") (pin "3") (pinfunction "1_3") (pintype "passive"))
    )
    (net (code "123") (name "Net-(R5D-1)") (class "Default")
      (node (ref "J1") (pin "4") (pinfunction "4_4") (pintype "bidirectional"))
      (node (ref "R5") (pin "4") (pinfunction "1_4") (pintype "passive"))
    )
    (net (code "124") (name "Net-(R6B-1)") (class "Default")
      (node (ref "J1") (pin "6") (pinfunction "6_6") (pintype "bidirectional"))
      (node (ref "R6") (pin "2") (pinfunction "1_2") (pintype "passive"))
    )
    (net (code "125") (name "Net-(R6C-1)") (class "Default")
      (node (ref "J1") (pin "7") (pinfunction "7_7") (pintype "bidirectional"))
      (node (ref "R6") (pin "3") (pinfunction "1_3") (pintype "passive"))
    )
    (net (code "126") (name "Net-(R6D-1)") (class "Default")
      (node (ref "J1") (pin "8") (pinfunction "8_8") (pintype "bidirectional"))
      (node (ref "R6") (pin "4") (pinfunction "1_4") (pintype "passive"))
    )
    (net (code "127") (name "Net-(R7B-1)") (class "Default")
      (node (ref "J1") (pin "10") (pinfunction "10_10") (pintype "bidirectional"))
      (node (ref "R7") (pin "2") (pinfunction "1_2") (pintype "passive"))
    )
    (net (code "128") (name "Net-(R7C-1)") (class "Default")
      (node (ref "J1") (pin "11") (pinfunction "11_11") (pintype "bidirectional"))
      (node (ref "R7") (pin "3") (pinfunction "1_3") (pintype "passive"))
    )
    (net (code "129") (name "Net-(R7D-1)") (class "Default")
      (node (ref "J1") (pin "12") (pinfunction "12_12") (pintype "bidirectional"))
      (node (ref "R7") (pin "4") (pinfunction "1_4") (pintype "passive"))
    )
    (net (code "130") (name "Net-(R8B-1)") (class "Default")
      (node (ref "J1") (pin "14") (pinfunction "14_14") (pintype "bidirectional"))
      (node (ref "R8") (pin "2") (pinfunction "1_2") (pintype "passive"))
    )
    (net (code "131") (name "Net-(R8C-1)") (class "Default")
      (node (ref "J1") (pin "15") (pinfunction "15_15") (pintype "bidirectional"))
      (node (ref "R8") (pin "3") (pinfunction "1_3") (pintype "passive"))
    )
    (net (code "132") (name "Net-(S1-S)") (class "Default")
      (node (ref "R21") (pin "1") (pinfunction "1_1") (pintype "passive"))
      (node (ref "S1") (pin "1") (pinfunction "S_1") (pintype "passive"))
      (node (ref "S1") (pin "2") (pinfunction "S1_2") (pintype "passive"))
      (node (ref "U1") (pin "94") (pinfunction "BOOT0_94") (pintype "bidirectional"))
    )
    (net (code "133") (name "Net-(SWD-RESET)") (class "Default")
      (node (ref "R4") (pin "1") (pinfunction "1_1") (pintype "passive"))
      (node (ref "SWD") (pin "10") (pinfunction "RESET_10") (pintype "bidirectional"))
      (node (ref "U1") (pin "14") (pinfunction "NRST_14") (pintype "bidirectional"))
    )
    (net (code "134") (name "Net-(U1-OSC_IN)") (class "Default")
      (node (ref "C11") (pin "1") (pinfunction "1_1") (pintype "passive"))
      (node (ref "Q1") (pin "1") (pinfunction "1_1") (pintype "passive"))
      (node (ref "U1") (pin "12") (pinfunction "OSC_IN_12") (pintype "bidirectional"))
    )
    (net (code "135") (name "Net-(U1-OSC_OUT)") (class "Default")
      (node (ref "C10") (pin "1") (pinfunction "1_1") (pintype "passive"))
      (node (ref "Q1") (pin "3") (pinfunction "3_3") (pintype "passive"))
      (node (ref "U1") (pin "13") (pinfunction "OSC_OUT_13") (pintype "bidirectional"))
    )
    (net (code "136") (name "Net-(U1-PA11)") (class "Default")
      (node (ref "R1") (pin "1") (pinfunction "1_1") (pintype "passive"))
      (node (ref "U1") (pin "70") (pinfunction "PA11_70") (pintype "bidirectional"))
    )
    (net (code "137") (name "Net-(U1-PA12)") (class "Default")
      (node (ref "R2") (pin "1") (pinfunction "1_1") (pintype "passive"))
      (node (ref "R3") (pin "1") (pinfunction "1_1") (pintype "passive"))
      (node (ref "U1") (pin "71") (pinfunction "PA12_71") (pintype "bidirectional"))
    )
    (net (code "138") (name "Net-(U1-PB2)") (class "Default")
      (node (ref "R20") (pin "2") (pinfunction "2_2") (pintype "passive"))
      (node (ref "U1") (pin "37") (pinfunction "PB2_37") (pintype "bidirectional"))
    )
    (net (code "139") (name "Net-(U2-BYPASS)") (class "Default")
      (node (ref "C8") (pin "1") (pinfunction "1_1") (pintype "passive"))
      (node (ref "U2") (pin "4") (pinfunction "BYPASS_4") (pintype "passive"))
    )
    (net (code "140") (name "Net-(X1-DM)") (class "Default")
      (node (ref "R1") (pin "2") (pinfunction "2_2") (pintype "passive"))
      (node (ref "X1") (pin "2") (pinfunction "DM_2") (pintype "bidirectional"))
    )
    (net (code "141") (name "Net-(X1-DP)") (class "Default")
      (node (ref "R2") (pin "2") (pinfunction "2_2") (pintype "passive"))
      (node (ref "X1") (pin "3") (pinfunction "DP_3") (pintype "bidirectional"))
    )
    (net (code "142") (name "unconnected-(SWD-KEY-Pad7)") (class "Default")
      (node (ref "SWD") (pin "7") (pinfunction "KEY_7") (pintype "bidirectional"))
    )
    (net (code "143") (name "unconnected-(SWD-TDI-Pad8)") (class "Default")
      (node (ref "SWD") (pin "8") (pinfunction "TDI_8") (pintype "bidirectional"))
    )
    (net (code "144") (name "unconnected-(U1-(OSC32_IN)PC14-Pad8)") (class "Default")
      (node (ref "U1") (pin "8") (pinfunction "(OSC32_IN)PC14_8") (pintype "bidirectional"))
    )
    (net (code "145") (name "unconnected-(U1-(TAMPER{slash}RTC)PC13-Pad7)") (class "Default")
      (node (ref "U1") (pin "7") (pinfunction "(TAMPER/RTC)PC13_7") (pintype "bidirectional"))
    )
    (net (code "146") (name "unconnected-(U1-NC-Pad73)") (class "Default")
      (node (ref "U1") (pin "73") (pinfunction "NC_73") (pintype "no_connect"))
    )
    (net (code "147") (name "unconnected-(U1-OSC32_OUT)PC15-Pad9)") (class "Default")
      (node (ref "U1") (pin "9") (pinfunction "OSC32_OUT)PC15_9") (pintype "bidirectional"))
    )
    (net (code "148") (name "unconnected-(U1-PC0-Pad15)") (class "Default")
      (node (ref "U1") (pin "15") (pinfunction "PC0_15") (pintype "bidirectional"))
    )
    (net (code "149") (name "unconnected-(U1-PC1-Pad16)") (class "Default")
      (node (ref "U1") (pin "16") (pinfunction "PC1_16") (pintype "bidirectional"))
    )
    (net (code "150") (name "unconnected-(U1-PC2-Pad17)") (class "Default")
      (node (ref "U1") (pin "17") (pinfunction "PC2_17") (pintype "bidirectional"))
    )
    (net (code "151") (name "unconnected-(U1-PC3-Pad18)") (class "Default")
      (node (ref "U1") (pin "18") (pinfunction "PC3_18") (pintype "bidirectional"))
    )
    (net (code "152") (name "unconnected-(U1-PE2-Pad1)") (class "Default")
      (node (ref "U1") (pin "1") (pinfunction "PE2_1") (pintype "bidirectional"))
    )
    (net (code "153") (name "unconnected-(U1-PE3-Pad2)") (class "Default")
      (node (ref "U1") (pin "2") (pinfunction "PE3_2") (pintype "bidirectional"))
    )
    (net (code "154") (name "unconnected-(U1-PE4-Pad3)") (class "Default")
      (node (ref "U1") (pin "3") (pinfunction "PE4_3") (pintype "bidirectional"))
    )
    (net (code "155") (name "unconnected-(U1-PE5-Pad4)") (class "Default")
      (node (ref "U1") (pin "4") (pinfunction "PE5_4") (pintype "bidirectional"))
    )
    (net (code "156") (name "unconnected-(U1-PE6-Pad5)") (class "Default")
      (node (ref "U1") (pin "5") (pinfunction "PE6_5") (pintype "bidirectional"))
    )
  )
)
